# amp1_psu_v0001.net
KiCad netlist of a schematic drawn in EAGLE
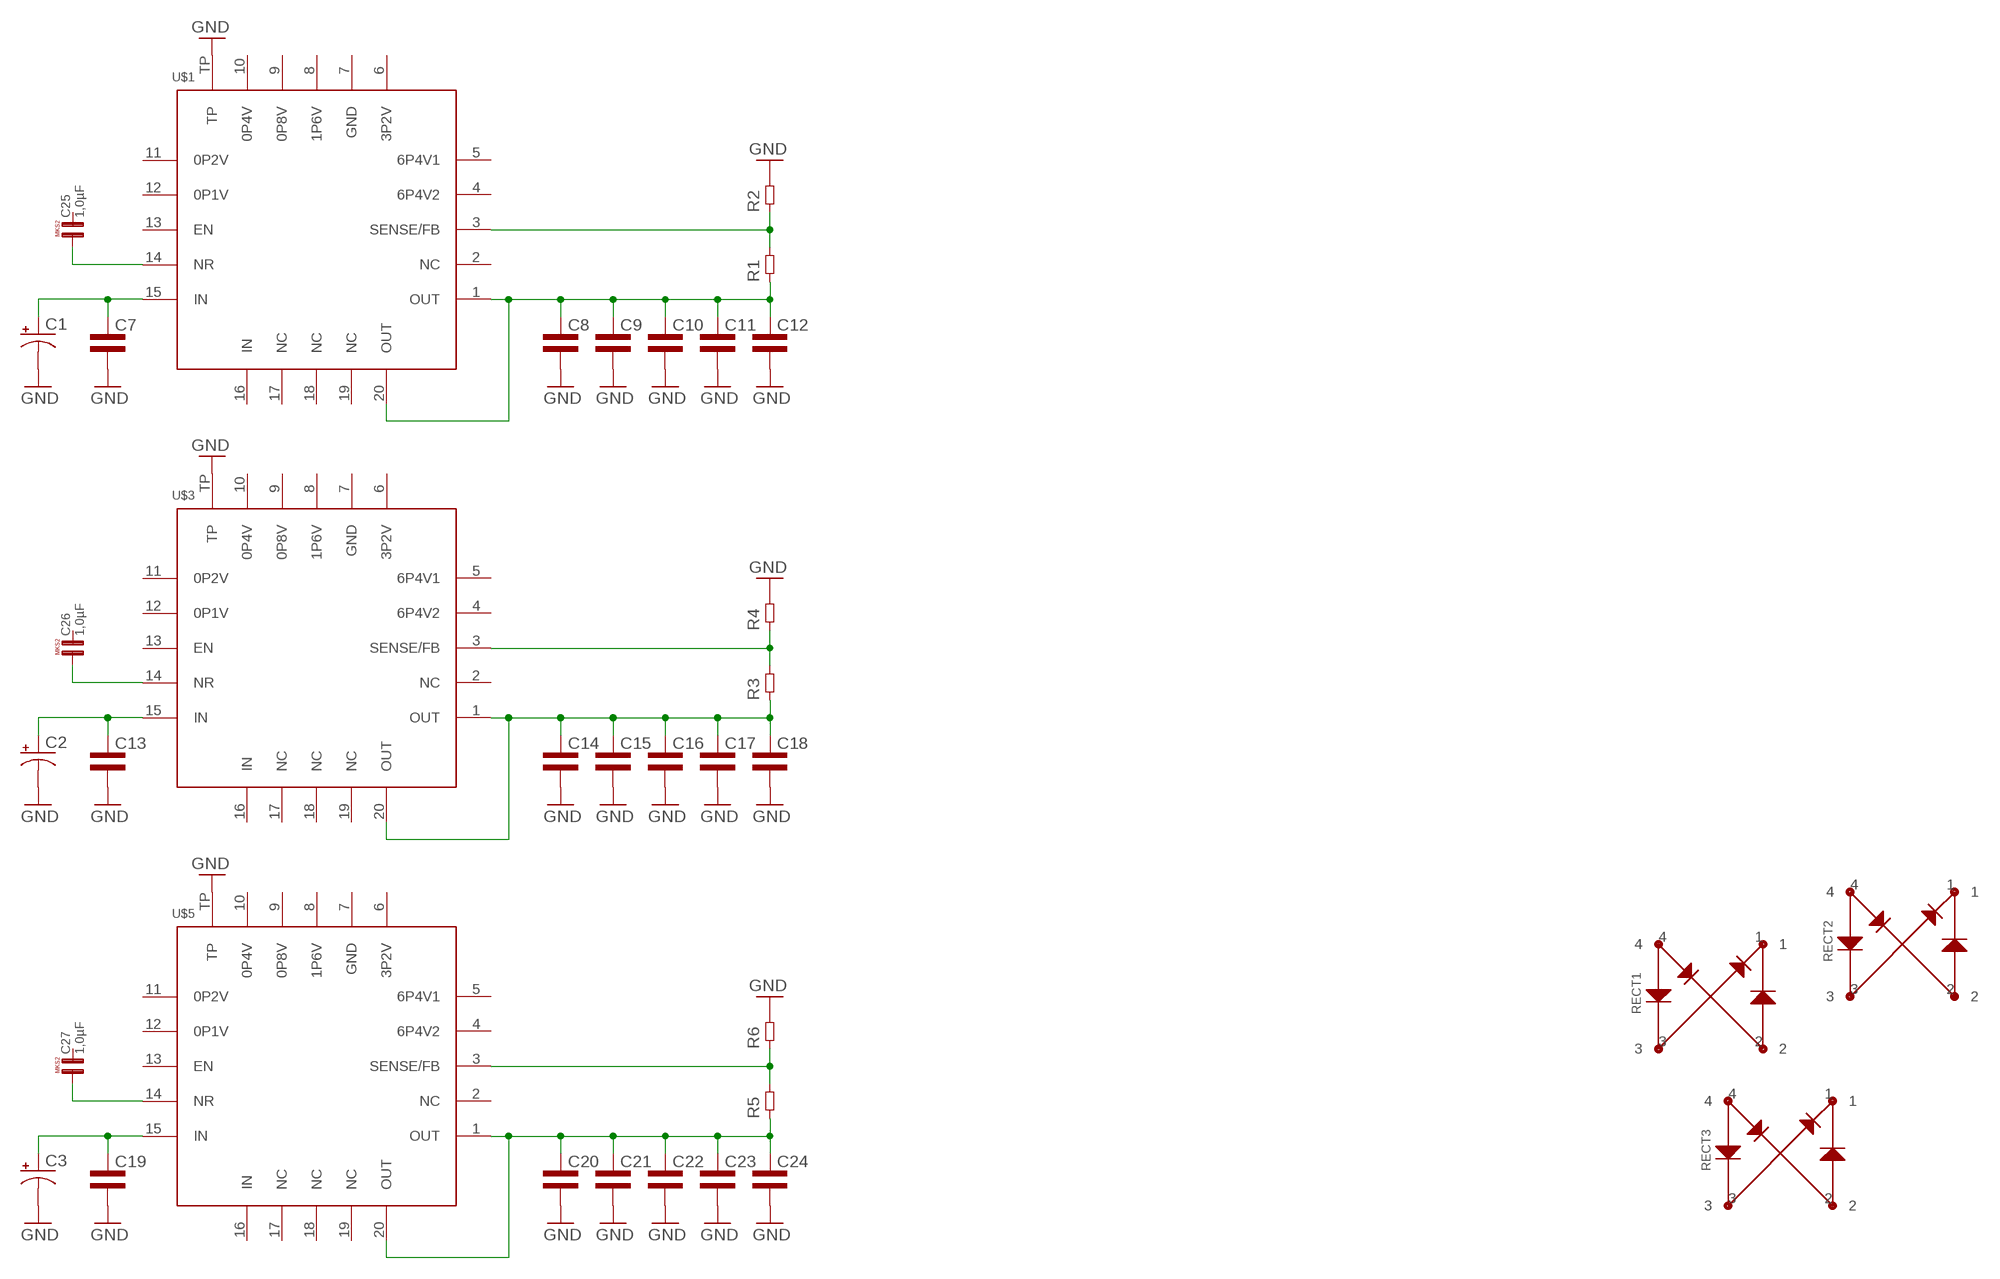
[diagram p0: schematic, sheet 1]
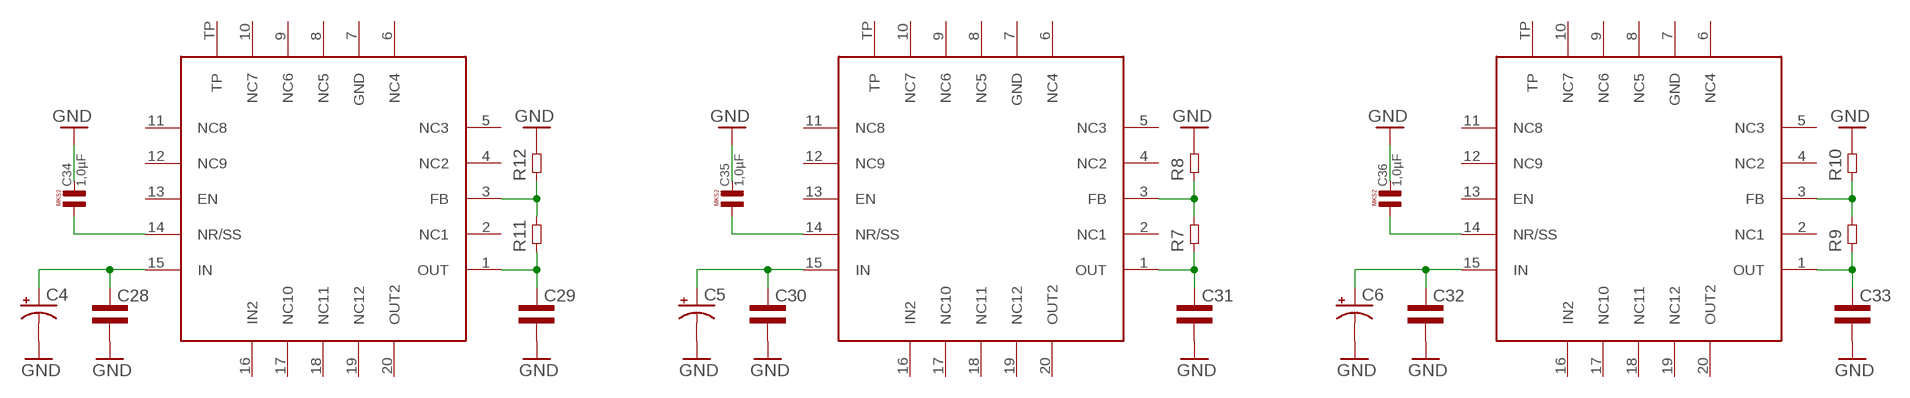
[diagram p1: schematic, sheet 2]

(export (version "E")
  (design (tool "Eeschema 10.0.6"))
  (components
    (comp (ref "C1")
      (value "CPOL-USE7.5-18")
      (footprint "eagle-import:E7,5-18")
      (libsource (lib "eagle-import") (part "CPOL-USE7.5-18"))
    )
    (comp (ref "C2")
      (value "CPOL-USE7.5-18")
      (footprint "eagle-import:E7,5-18")
      (libsource (lib "eagle-import") (part "CPOL-USE7.5-18"))
    )
    (comp (ref "C3")
      (value "CPOL-USE7.5-18")
      (footprint "eagle-import:E7,5-18")
      (libsource (lib "eagle-import") (part "CPOL-USE7.5-18"))
    )
    (comp (ref "C7")
      (value "CAP0805L3")
      (footprint "eagle-import:0805L3")
      (libsource (lib "eagle-import") (part "CAP0805L3"))
    )
    (comp (ref "C8")
      (value "CAP0805L3")
      (footprint "eagle-import:0805L3")
      (libsource (lib "eagle-import") (part "CAP0805L3"))
    )
    (comp (ref "C9")
      (value "CAP0805L3")
      (footprint "eagle-import:0805L3")
      (libsource (lib "eagle-import") (part "CAP0805L3"))
    )
    (comp (ref "C10")
      (value "CAP0805L3")
      (footprint "eagle-import:0805L3")
      (libsource (lib "eagle-import") (part "CAP0805L3"))
    )
    (comp (ref "C11")
      (value "CAP0805L3")
      (footprint "eagle-import:0805L3")
      (libsource (lib "eagle-import") (part "CAP0805L3"))
    )
    (comp (ref "C12")
      (value "CAP0805L3")
      (footprint "eagle-import:0805L3")
      (libsource (lib "eagle-import") (part "CAP0805L3"))
    )
    (comp (ref "C13")
      (value "CAP0805L3")
      (footprint "eagle-import:0805L3")
      (libsource (lib "eagle-import") (part "CAP0805L3"))
    )
    (comp (ref "C14")
      (value "CAP0805L3")
      (footprint "eagle-import:0805L3")
      (libsource (lib "eagle-import") (part "CAP0805L3"))
    )
    (comp (ref "C15")
      (value "CAP0805L3")
      (footprint "eagle-import:0805L3")
      (libsource (lib "eagle-import") (part "CAP0805L3"))
    )
    (comp (ref "C16")
      (value "CAP0805L3")
      (footprint "eagle-import:0805L3")
      (libsource (lib "eagle-import") (part "CAP0805L3"))
    )
    (comp (ref "C17")
      (value "CAP0805L3")
      (footprint "eagle-import:0805L3")
      (libsource (lib "eagle-import") (part "CAP0805L3"))
    )
    (comp (ref "C18")
      (value "CAP0805L3")
      (footprint "eagle-import:0805L3")
      (libsource (lib "eagle-import") (part "CAP0805L3"))
    )
    (comp (ref "C19")
      (value "CAP0805L3")
      (footprint "eagle-import:0805L3")
      (libsource (lib "eagle-import") (part "CAP0805L3"))
    )
    (comp (ref "C20")
      (value "CAP0805L3")
      (footprint "eagle-import:0805L3")
      (libsource (lib "eagle-import") (part "CAP0805L3"))
    )
    (comp (ref "C21")
      (value "CAP0805L3")
      (footprint "eagle-import:0805L3")
      (libsource (lib "eagle-import") (part "CAP0805L3"))
    )
    (comp (ref "C22")
      (value "CAP0805L3")
      (footprint "eagle-import:0805L3")
      (libsource (lib "eagle-import") (part "CAP0805L3"))
    )
    (comp (ref "C23")
      (value "CAP0805L3")
      (footprint "eagle-import:0805L3")
      (libsource (lib "eagle-import") (part "CAP0805L3"))
    )
    (comp (ref "C24")
      (value "CAP0805L3")
      (footprint "eagle-import:0805L3")
      (libsource (lib "eagle-import") (part "CAP0805L3"))
    )
    (comp (ref "C25")
      (value "1,0µF")
      (footprint "eagle-import:R5B5")
      (libsource (lib "eagle-import") (part "1,0µF"))
    )
    (comp (ref "C26")
      (value "1,0µF")
      (footprint "eagle-import:R5B5")
      (libsource (lib "eagle-import") (part "1,0µF"))
    )
    (comp (ref "C27")
      (value "1,0µF")
      (footprint "eagle-import:R5B5")
      (libsource (lib "eagle-import") (part "1,0µF"))
    )
    (comp (ref "R1")
      (value "RES0805L3")
      (footprint "eagle-import:0805L3")
      (libsource (lib "eagle-import") (part "RES0805L3"))
    )
    (comp (ref "R2")
      (value "RES0805L3")
      (footprint "eagle-import:0805L3")
      (libsource (lib "eagle-import") (part "RES0805L3"))
    )
    (comp (ref "R3")
      (value "RES0805L3")
      (footprint "eagle-import:0805L3")
      (libsource (lib "eagle-import") (part "RES0805L3"))
    )
    (comp (ref "R4")
      (value "RES0805L3")
      (footprint "eagle-import:0805L3")
      (libsource (lib "eagle-import") (part "RES0805L3"))
    )
    (comp (ref "R5")
      (value "RES0805L3")
      (footprint "eagle-import:0805L3")
      (libsource (lib "eagle-import") (part "RES0805L3"))
    )
    (comp (ref "R6")
      (value "RES0805L3")
      (footprint "eagle-import:0805L3")
      (libsource (lib "eagle-import") (part "RES0805L3"))
    )
    (comp (ref "RECT1")
      (value "RECTIFIER_Z4GP206")
      (footprint "eagle-import:RECTIFIER_ABS-4")
      (libsource (lib "eagle-import") (part "RECTIFIER_Z4GP206"))
    )
    (comp (ref "RECT2")
      (value "RECTIFIER_Z4GP206")
      (footprint "eagle-import:RECTIFIER_ABS-4")
      (libsource (lib "eagle-import") (part "RECTIFIER_Z4GP206"))
    )
    (comp (ref "RECT3")
      (value "RECTIFIER_Z4GP206")
      (footprint "eagle-import:RECTIFIER_ABS-4")
      (libsource (lib "eagle-import") (part "RECTIFIER_Z4GP206"))
    )
    (comp (ref "U$1")
      (value "POWER-SUPPLY_POS_V1_TI_LDO_TPS7A4700")
      (footprint "eagle-import:POWER-SUPPLY_POS_V1_TI_LDO_VQFN-20")
      (libsource (lib "eagle-import") (part "POWER-SUPPLY_POS_V1_TI_LDO_TPS7A4700"))
    )
    (comp (ref "U$3")
      (value "POWER-SUPPLY_POS_V1_TI_LDO_TPS7A4700")
      (footprint "eagle-import:POWER-SUPPLY_POS_V1_TI_LDO_VQFN-20")
      (libsource (lib "eagle-import") (part "POWER-SUPPLY_POS_V1_TI_LDO_TPS7A4700"))
    )
    (comp (ref "U$5")
      (value "POWER-SUPPLY_POS_V1_TI_LDO_TPS7A4700")
      (footprint "eagle-import:POWER-SUPPLY_POS_V1_TI_LDO_VQFN-20")
      (libsource (lib "eagle-import") (part "POWER-SUPPLY_POS_V1_TI_LDO_TPS7A4700"))
    )
    (comp (ref "C4")
      (value "CPOL-USE7.5-18")
      (footprint "eagle-import:E7,5-18")
      (libsource (lib "eagle-import") (part "CPOL-USE7.5-18"))
    )
    (comp (ref "C5")
      (value "CPOL-USE7.5-18")
      (footprint "eagle-import:E7,5-18")
      (libsource (lib "eagle-import") (part "CPOL-USE7.5-18"))
    )
    (comp (ref "C6")
      (value "CPOL-USE7.5-18")
      (footprint "eagle-import:E7,5-18")
      (libsource (lib "eagle-import") (part "CPOL-USE7.5-18"))
    )
    (comp (ref "C28")
      (value "CAP0805L3")
      (footprint "eagle-import:0805L3")
      (libsource (lib "eagle-import") (part "CAP0805L3"))
    )
    (comp (ref "C29")
      (value "CAP0805L3")
      (footprint "eagle-import:0805L3")
      (libsource (lib "eagle-import") (part "CAP0805L3"))
    )
    (comp (ref "C30")
      (value "CAP0805L3")
      (footprint "eagle-import:0805L3")
      (libsource (lib "eagle-import") (part "CAP0805L3"))
    )
    (comp (ref "C31")
      (value "CAP0805L3")
      (footprint "eagle-import:0805L3")
      (libsource (lib "eagle-import") (part "CAP0805L3"))
    )
    (comp (ref "C32")
      (value "CAP0805L3")
      (footprint "eagle-import:0805L3")
      (libsource (lib "eagle-import") (part "CAP0805L3"))
    )
    (comp (ref "C33")
      (value "CAP0805L3")
      (footprint "eagle-import:0805L3")
      (libsource (lib "eagle-import") (part "CAP0805L3"))
    )
    (comp (ref "C34")
      (value "1,0µF")
      (footprint "eagle-import:R5B5")
      (libsource (lib "eagle-import") (part "1,0µF"))
    )
    (comp (ref "C35")
      (value "1,0µF")
      (footprint "eagle-import:R5B5")
      (libsource (lib "eagle-import") (part "1,0µF"))
    )
    (comp (ref "C36")
      (value "1,0µF")
      (footprint "eagle-import:R5B5")
      (libsource (lib "eagle-import") (part "1,0µF"))
    )
    (comp (ref "R7")
      (value "RES0805L3")
      (footprint "eagle-import:0805L3")
      (libsource (lib "eagle-import") (part "RES0805L3"))
    )
    (comp (ref "R8")
      (value "RES0805L3")
      (footprint "eagle-import:0805L3")
      (libsource (lib "eagle-import") (part "RES0805L3"))
    )
    (comp (ref "R9")
      (value "RES0805L3")
      (footprint "eagle-import:0805L3")
      (libsource (lib "eagle-import") (part "RES0805L3"))
    )
    (comp (ref "R10")
      (value "RES0805L3")
      (footprint "eagle-import:0805L3")
      (libsource (lib "eagle-import") (part "RES0805L3"))
    )
    (comp (ref "R11")
      (value "RES0805L3")
      (footprint "eagle-import:0805L3")
      (libsource (lib "eagle-import") (part "RES0805L3"))
    )
    (comp (ref "R12")
      (value "RES0805L3")
      (footprint "eagle-import:0805L3")
      (libsource (lib "eagle-import") (part "RES0805L3"))
    )
    (comp (ref "U$6")
      (value "POWER-SUPPLY_POS_V1_TI_LDO_TPS7A3301RGWT")
      (footprint "eagle-import:POWER-SUPPLY_POS_V1_TI_LDO_VQFN-20")
      (libsource (lib "eagle-import") (part "POWER-SUPPLY_POS_V1_TI_LDO_TPS7A3301RGWT"))
    )
    (comp (ref "U$7")
      (value "POWER-SUPPLY_POS_V1_TI_LDO_TPS7A3301RGWT")
      (footprint "eagle-import:POWER-SUPPLY_POS_V1_TI_LDO_VQFN-20")
      (libsource (lib "eagle-import") (part "POWER-SUPPLY_POS_V1_TI_LDO_TPS7A3301RGWT"))
    )
    (comp (ref "U$8")
      (value "POWER-SUPPLY_POS_V1_TI_LDO_TPS7A3301RGWT")
      (footprint "eagle-import:POWER-SUPPLY_POS_V1_TI_LDO_VQFN-20")
      (libsource (lib "eagle-import") (part "POWER-SUPPLY_POS_V1_TI_LDO_TPS7A3301RGWT"))
    )
  )
  (nets
    (net (code "1") (name "GND") (class "Default")
      (node (ref "C1") (pin "-") (pinfunction "-_-") (pintype "passive"))
      (node (ref "C10") (pin "2") (pinfunction "2_2") (pintype "bidirectional"))
      (node (ref "C11") (pin "2") (pinfunction "2_2") (pintype "bidirectional"))
      (node (ref "C12") (pin "2") (pinfunction "2_2") (pintype "bidirectional"))
      (node (ref "C13") (pin "2") (pinfunction "2_2") (pintype "bidirectional"))
      (node (ref "C14") (pin "2") (pinfunction "2_2") (pintype "bidirectional"))
      (node (ref "C15") (pin "2") (pinfunction "2_2") (pintype "bidirectional"))
      (node (ref "C16") (pin "2") (pinfunction "2_2") (pintype "bidirectional"))
      (node (ref "C17") (pin "2") (pinfunction "2_2") (pintype "bidirectional"))
      (node (ref "C18") (pin "2") (pinfunction "2_2") (pintype "bidirectional"))
      (node (ref "C19") (pin "2") (pinfunction "2_2") (pintype "bidirectional"))
      (node (ref "C2") (pin "-") (pinfunction "-_-") (pintype "passive"))
      (node (ref "C20") (pin "2") (pinfunction "2_2") (pintype "bidirectional"))
      (node (ref "C21") (pin "2") (pinfunction "2_2") (pintype "bidirectional"))
      (node (ref "C22") (pin "2") (pinfunction "2_2") (pintype "bidirectional"))
      (node (ref "C23") (pin "2") (pinfunction "2_2") (pintype "bidirectional"))
      (node (ref "C24") (pin "2") (pinfunction "2_2") (pintype "bidirectional"))
      (node (ref "C28") (pin "2") (pinfunction "2_2") (pintype "bidirectional"))
      (node (ref "C29") (pin "2") (pinfunction "2_2") (pintype "bidirectional"))
      (node (ref "C3") (pin "-") (pinfunction "-_-") (pintype "passive"))
      (node (ref "C30") (pin "2") (pinfunction "2_2") (pintype "bidirectional"))
      (node (ref "C31") (pin "2") (pinfunction "2_2") (pintype "bidirectional"))
      (node (ref "C32") (pin "2") (pinfunction "2_2") (pintype "bidirectional"))
      (node (ref "C33") (pin "2") (pinfunction "2_2") (pintype "bidirectional"))
      (node (ref "C34") (pin "2") (pinfunction "2_2") (pintype "passive"))
      (node (ref "C35") (pin "2") (pinfunction "2_2") (pintype "passive"))
      (node (ref "C36") (pin "2") (pinfunction "2_2") (pintype "passive"))
      (node (ref "C4") (pin "-") (pinfunction "-_-") (pintype "passive"))
      (node (ref "C5") (pin "-") (pinfunction "-_-") (pintype "passive"))
      (node (ref "C6") (pin "-") (pinfunction "-_-") (pintype "passive"))
      (node (ref "C7") (pin "2") (pinfunction "2_2") (pintype "bidirectional"))
      (node (ref "C8") (pin "2") (pinfunction "2_2") (pintype "bidirectional"))
      (node (ref "C9") (pin "2") (pinfunction "2_2") (pintype "bidirectional"))
      (node (ref "R10") (pin "2") (pinfunction "2_2") (pintype "bidirectional"))
      (node (ref "R12") (pin "2") (pinfunction "2_2") (pintype "bidirectional"))
      (node (ref "R2") (pin "2") (pinfunction "2_2") (pintype "bidirectional"))
      (node (ref "R4") (pin "2") (pinfunction "2_2") (pintype "bidirectional"))
      (node (ref "R6") (pin "2") (pinfunction "2_2") (pintype "bidirectional"))
      (node (ref "R8") (pin "2") (pinfunction "2_2") (pintype "bidirectional"))
      (node (ref "U$1") (pin "TP") (pinfunction "TP_TP") (pintype "bidirectional"))
      (node (ref "U$3") (pin "TP") (pinfunction "TP_TP") (pintype "bidirectional"))
      (node (ref "U$5") (pin "TP") (pinfunction "TP_TP") (pintype "bidirectional"))
    )
    (net (code "2") (name "Net-(C1-Pad+)") (class "Default")
      (node (ref "C1") (pin "+") (pinfunction "+_+") (pintype "passive"))
      (node (ref "C7") (pin "1") (pinfunction "1_1") (pintype "bidirectional"))
      (node (ref "U$1") (pin "15") (pinfunction "IN_15") (pintype "bidirectional"))
    )
    (net (code "3") (name "Net-(C10-Pad1)") (class "Default")
      (node (ref "C10") (pin "1") (pinfunction "1_1") (pintype "bidirectional"))
      (node (ref "C11") (pin "1") (pinfunction "1_1") (pintype "bidirectional"))
      (node (ref "C12") (pin "1") (pinfunction "1_1") (pintype "bidirectional"))
      (node (ref "C8") (pin "1") (pinfunction "1_1") (pintype "bidirectional"))
      (node (ref "C9") (pin "1") (pinfunction "1_1") (pintype "bidirectional"))
      (node (ref "R1") (pin "1") (pinfunction "1_1") (pintype "bidirectional"))
      (node (ref "U$1") (pin "1") (pinfunction "OUT_1") (pintype "bidirectional"))
      (node (ref "U$1") (pin "20") (pinfunction "OUT_20") (pintype "bidirectional"))
    )
    (net (code "4") (name "Net-(C13-Pad1)") (class "Default")
      (node (ref "C13") (pin "1") (pinfunction "1_1") (pintype "bidirectional"))
      (node (ref "C2") (pin "+") (pinfunction "+_+") (pintype "passive"))
      (node (ref "U$3") (pin "15") (pinfunction "IN_15") (pintype "bidirectional"))
    )
    (net (code "5") (name "Net-(C14-Pad1)") (class "Default")
      (node (ref "C14") (pin "1") (pinfunction "1_1") (pintype "bidirectional"))
      (node (ref "C15") (pin "1") (pinfunction "1_1") (pintype "bidirectional"))
      (node (ref "C16") (pin "1") (pinfunction "1_1") (pintype "bidirectional"))
      (node (ref "C17") (pin "1") (pinfunction "1_1") (pintype "bidirectional"))
      (node (ref "C18") (pin "1") (pinfunction "1_1") (pintype "bidirectional"))
      (node (ref "R3") (pin "1") (pinfunction "1_1") (pintype "bidirectional"))
      (node (ref "U$3") (pin "1") (pinfunction "OUT_1") (pintype "bidirectional"))
      (node (ref "U$3") (pin "20") (pinfunction "OUT_20") (pintype "bidirectional"))
    )
    (net (code "6") (name "Net-(C19-Pad1)") (class "Default")
      (node (ref "C19") (pin "1") (pinfunction "1_1") (pintype "bidirectional"))
      (node (ref "C3") (pin "+") (pinfunction "+_+") (pintype "passive"))
      (node (ref "U$5") (pin "15") (pinfunction "IN_15") (pintype "bidirectional"))
    )
    (net (code "7") (name "Net-(C20-Pad1)") (class "Default")
      (node (ref "C20") (pin "1") (pinfunction "1_1") (pintype "bidirectional"))
      (node (ref "C21") (pin "1") (pinfunction "1_1") (pintype "bidirectional"))
      (node (ref "C22") (pin "1") (pinfunction "1_1") (pintype "bidirectional"))
      (node (ref "C23") (pin "1") (pinfunction "1_1") (pintype "bidirectional"))
      (node (ref "C24") (pin "1") (pinfunction "1_1") (pintype "bidirectional"))
      (node (ref "R5") (pin "1") (pinfunction "1_1") (pintype "bidirectional"))
      (node (ref "U$5") (pin "1") (pinfunction "OUT_1") (pintype "bidirectional"))
      (node (ref "U$5") (pin "20") (pinfunction "OUT_20") (pintype "bidirectional"))
    )
    (net (code "8") (name "Net-(U$1-NR)") (class "Default")
      (node (ref "C25") (pin "1") (pinfunction "1_1") (pintype "passive"))
      (node (ref "U$1") (pin "14") (pinfunction "NR_14") (pintype "bidirectional"))
    )
    (net (code "9") (name "Net-(U$1-SENSE{slash}FB)") (class "Default")
      (node (ref "R1") (pin "2") (pinfunction "2_2") (pintype "bidirectional"))
      (node (ref "R2") (pin "1") (pinfunction "1_1") (pintype "bidirectional"))
      (node (ref "U$1") (pin "3") (pinfunction "SENSE/FB_3") (pintype "bidirectional"))
    )
    (net (code "10") (name "Net-(U$3-NR)") (class "Default")
      (node (ref "C26") (pin "1") (pinfunction "1_1") (pintype "passive"))
      (node (ref "U$3") (pin "14") (pinfunction "NR_14") (pintype "bidirectional"))
    )
    (net (code "11") (name "Net-(U$3-SENSE{slash}FB)") (class "Default")
      (node (ref "R3") (pin "2") (pinfunction "2_2") (pintype "bidirectional"))
      (node (ref "R4") (pin "1") (pinfunction "1_1") (pintype "bidirectional"))
      (node (ref "U$3") (pin "3") (pinfunction "SENSE/FB_3") (pintype "bidirectional"))
    )
    (net (code "12") (name "Net-(U$5-NR)") (class "Default")
      (node (ref "C27") (pin "1") (pinfunction "1_1") (pintype "passive"))
      (node (ref "U$5") (pin "14") (pinfunction "NR_14") (pintype "bidirectional"))
    )
    (net (code "13") (name "Net-(U$5-SENSE{slash}FB)") (class "Default")
      (node (ref "R5") (pin "2") (pinfunction "2_2") (pintype "bidirectional"))
      (node (ref "R6") (pin "1") (pinfunction "1_1") (pintype "bidirectional"))
      (node (ref "U$5") (pin "3") (pinfunction "SENSE/FB_3") (pintype "bidirectional"))
    )
    (net (code "14") (name "Net-(U$6-FB)") (class "Default")
      (node (ref "R11") (pin "2") (pinfunction "2_2") (pintype "bidirectional"))
      (node (ref "R12") (pin "1") (pinfunction "1_1") (pintype "bidirectional"))
      (node (ref "U$6") (pin "3") (pinfunction "FB_3") (pintype "bidirectional"))
    )
    (net (code "15") (name "Net-(U$6-IN)") (class "Default")
      (node (ref "C28") (pin "1") (pinfunction "1_1") (pintype "bidirectional"))
      (node (ref "C4") (pin "+") (pinfunction "+_+") (pintype "passive"))
      (node (ref "U$6") (pin "15") (pinfunction "IN_15") (pintype "bidirectional"))
    )
    (net (code "16") (name "Net-(U$6-NR{slash}SS)") (class "Default")
      (node (ref "C34") (pin "1") (pinfunction "1_1") (pintype "passive"))
      (node (ref "U$6") (pin "14") (pinfunction "NR/SS_14") (pintype "bidirectional"))
    )
    (net (code "17") (name "Net-(U$6-OUT)") (class "Default")
      (node (ref "C29") (pin "1") (pinfunction "1_1") (pintype "bidirectional"))
      (node (ref "R11") (pin "1") (pinfunction "1_1") (pintype "bidirectional"))
      (node (ref "U$6") (pin "1") (pinfunction "OUT_1") (pintype "bidirectional"))
    )
    (net (code "18") (name "Net-(U$7-FB)") (class "Default")
      (node (ref "R7") (pin "2") (pinfunction "2_2") (pintype "bidirectional"))
      (node (ref "R8") (pin "1") (pinfunction "1_1") (pintype "bidirectional"))
      (node (ref "U$7") (pin "3") (pinfunction "FB_3") (pintype "bidirectional"))
    )
    (net (code "19") (name "Net-(U$7-IN)") (class "Default")
      (node (ref "C30") (pin "1") (pinfunction "1_1") (pintype "bidirectional"))
      (node (ref "C5") (pin "+") (pinfunction "+_+") (pintype "passive"))
      (node (ref "U$7") (pin "15") (pinfunction "IN_15") (pintype "bidirectional"))
    )
    (net (code "20") (name "Net-(U$7-NR{slash}SS)") (class "Default")
      (node (ref "C35") (pin "1") (pinfunction "1_1") (pintype "passive"))
      (node (ref "U$7") (pin "14") (pinfunction "NR/SS_14") (pintype "bidirectional"))
    )
    (net (code "21") (name "Net-(U$7-OUT)") (class "Default")
      (node (ref "C31") (pin "1") (pinfunction "1_1") (pintype "bidirectional"))
      (node (ref "R7") (pin "1") (pinfunction "1_1") (pintype "bidirectional"))
      (node (ref "U$7") (pin "1") (pinfunction "OUT_1") (pintype "bidirectional"))
    )
    (net (code "22") (name "Net-(U$8-FB)") (class "Default")
      (node (ref "R10") (pin "1") (pinfunction "1_1") (pintype "bidirectional"))
      (node (ref "R9") (pin "2") (pinfunction "2_2") (pintype "bidirectional"))
      (node (ref "U$8") (pin "3") (pinfunction "FB_3") (pintype "bidirectional"))
    )
    (net (code "23") (name "Net-(U$8-IN)") (class "Default")
      (node (ref "C32") (pin "1") (pinfunction "1_1") (pintype "bidirectional"))
      (node (ref "C6") (pin "+") (pinfunction "+_+") (pintype "passive"))
      (node (ref "U$8") (pin "15") (pinfunction "IN_15") (pintype "bidirectional"))
    )
    (net (code "24") (name "Net-(U$8-NR{slash}SS)") (class "Default")
      (node (ref "C36") (pin "1") (pinfunction "1_1") (pintype "passive"))
      (node (ref "U$8") (pin "14") (pinfunction "NR/SS_14") (pintype "bidirectional"))
    )
    (net (code "25") (name "Net-(U$8-OUT)") (class "Default")
      (node (ref "C33") (pin "1") (pinfunction "1_1") (pintype "bidirectional"))
      (node (ref "R9") (pin "1") (pinfunction "1_1") (pintype "bidirectional"))
      (node (ref "U$8") (pin "1") (pinfunction "OUT_1") (pintype "bidirectional"))
    )
    (net (code "26") (name "unconnected-(C25-Pad2)") (class "Default")
      (node (ref "C25") (pin "2") (pinfunction "2_2") (pintype "passive"))
    )
    (net (code "27") (name "unconnected-(C26-Pad2)") (class "Default")
      (node (ref "C26") (pin "2") (pinfunction "2_2") (pintype "passive"))
    )
    (net (code "28") (name "unconnected-(C27-Pad2)") (class "Default")
      (node (ref "C27") (pin "2") (pinfunction "2_2") (pintype "passive"))
    )
    (net (code "29") (name "unconnected-(RECT1-Pad1)") (class "Default")
      (node (ref "RECT1") (pin "1") (pinfunction "1_1") (pintype "bidirectional"))
    )
    (net (code "30") (name "unconnected-(RECT1-Pad2)") (class "Default")
      (node (ref "RECT1") (pin "2") (pinfunction "2_2") (pintype "bidirectional"))
    )
    (net (code "31") (name "unconnected-(RECT1-Pad3)") (class "Default")
      (node (ref "RECT1") (pin "3") (pinfunction "3_3") (pintype "bidirectional"))
    )
    (net (code "32") (name "unconnected-(RECT1-Pad4)") (class "Default")
      (node (ref "RECT1") (pin "4") (pinfunction "4_4") (pintype "bidirectional"))
    )
    (net (code "33") (name "unconnected-(RECT2-Pad1)") (class "Default")
      (node (ref "RECT2") (pin "1") (pinfunction "1_1") (pintype "bidirectional"))
    )
    (net (code "34") (name "unconnected-(RECT2-Pad2)") (class "Default")
      (node (ref "RECT2") (pin "2") (pinfunction "2_2") (pintype "bidirectional"))
    )
    (net (code "35") (name "unconnected-(RECT2-Pad3)") (class "Default")
      (node (ref "RECT2") (pin "3") (pinfunction "3_3") (pintype "bidirectional"))
    )
    (net (code "36") (name "unconnected-(RECT2-Pad4)") (class "Default")
      (node (ref "RECT2") (pin "4") (pinfunction "4_4") (pintype "bidirectional"))
    )
    (net (code "37") (name "unconnected-(RECT3-Pad1)") (class "Default")
      (node (ref "RECT3") (pin "1") (pinfunction "1_1") (pintype "bidirectional"))
    )
    (net (code "38") (name "unconnected-(RECT3-Pad2)") (class "Default")
      (node (ref "RECT3") (pin "2") (pinfunction "2_2") (pintype "bidirectional"))
    )
    (net (code "39") (name "unconnected-(RECT3-Pad3)") (class "Default")
      (node (ref "RECT3") (pin "3") (pinfunction "3_3") (pintype "bidirectional"))
    )
    (net (code "40") (name "unconnected-(RECT3-Pad4)") (class "Default")
      (node (ref "RECT3") (pin "4") (pinfunction "4_4") (pintype "bidirectional"))
    )
    (net (code "41") (name "unconnected-(U$1-0P1V-Pad12)") (class "Default")
      (node (ref "U$1") (pin "12") (pinfunction "0P1V_12") (pintype "bidirectional"))
    )
    (net (code "42") (name "unconnected-(U$1-0P2V-Pad11)") (class "Default")
      (node (ref "U$1") (pin "11") (pinfunction "0P2V_11") (pintype "bidirectional"))
    )
    (net (code "43") (name "unconnected-(U$1-0P4V-Pad10)") (class "Default")
      (node (ref "U$1") (pin "10") (pinfunction "0P4V_10") (pintype "bidirectional"))
    )
    (net (code "44") (name "unconnected-(U$1-0P8V-Pad9)") (class "Default")
      (node (ref "U$1") (pin "9") (pinfunction "0P8V_9") (pintype "bidirectional"))
    )
    (net (code "45") (name "unconnected-(U$1-1P6V-Pad8)") (class "Default")
      (node (ref "U$1") (pin "8") (pinfunction "1P6V_8") (pintype "bidirectional"))
    )
    (net (code "46") (name "unconnected-(U$1-3P2V-Pad6)") (class "Default")
      (node (ref "U$1") (pin "6") (pinfunction "3P2V_6") (pintype "bidirectional"))
    )
    (net (code "47") (name "unconnected-(U$1-6P4V1-Pad5)") (class "Default")
      (node (ref "U$1") (pin "5") (pinfunction "6P4V1_5") (pintype "bidirectional"))
    )
    (net (code "48") (name "unconnected-(U$1-6P4V2-Pad4)") (class "Default")
      (node (ref "U$1") (pin "4") (pinfunction "6P4V2_4") (pintype "bidirectional"))
    )
    (net (code "49") (name "unconnected-(U$1-EN-Pad13)") (class "Default")
      (node (ref "U$1") (pin "13") (pinfunction "EN_13") (pintype "bidirectional"))
    )
    (net (code "50") (name "unconnected-(U$1-GND-Pad7)") (class "Default")
      (node (ref "U$1") (pin "7") (pinfunction "GND_7") (pintype "bidirectional"))
    )
    (net (code "51") (name "unconnected-(U$1-IN-Pad16)") (class "Default")
      (node (ref "U$1") (pin "16") (pinfunction "IN_16") (pintype "bidirectional"))
    )
    (net (code "52") (name "unconnected-(U$1-NC-Pad2)") (class "Default")
      (node (ref "U$1") (pin "2") (pinfunction "NC_2") (pintype "bidirectional"))
    )
    (net (code "53") (name "unconnected-(U$1-NC-Pad17)") (class "Default")
      (node (ref "U$1") (pin "17") (pinfunction "NC_17") (pintype "bidirectional"))
    )
    (net (code "54") (name "unconnected-(U$1-NC-Pad18)") (class "Default")
      (node (ref "U$1") (pin "18") (pinfunction "NC_18") (pintype "bidirectional"))
    )
    (net (code "55") (name "unconnected-(U$1-NC-Pad19)") (class "Default")
      (node (ref "U$1") (pin "19") (pinfunction "NC_19") (pintype "bidirectional"))
    )
    (net (code "56") (name "unconnected-(U$3-0P1V-Pad12)") (class "Default")
      (node (ref "U$3") (pin "12") (pinfunction "0P1V_12") (pintype "bidirectional"))
    )
    (net (code "57") (name "unconnected-(U$3-0P2V-Pad11)") (class "Default")
      (node (ref "U$3") (pin "11") (pinfunction "0P2V_11") (pintype "bidirectional"))
    )
    (net (code "58") (name "unconnected-(U$3-0P4V-Pad10)") (class "Default")
      (node (ref "U$3") (pin "10") (pinfunction "0P4V_10") (pintype "bidirectional"))
    )
    (net (code "59") (name "unconnected-(U$3-0P8V-Pad9)") (class "Default")
      (node (ref "U$3") (pin "9") (pinfunction "0P8V_9") (pintype "bidirectional"))
    )
    (net (code "60") (name "unconnected-(U$3-1P6V-Pad8)") (class "Default")
      (node (ref "U$3") (pin "8") (pinfunction "1P6V_8") (pintype "bidirectional"))
    )
    (net (code "61") (name "unconnected-(U$3-3P2V-Pad6)") (class "Default")
      (node (ref "U$3") (pin "6") (pinfunction "3P2V_6") (pintype "bidirectional"))
    )
    (net (code "62") (name "unconnected-(U$3-6P4V1-Pad5)") (class "Default")
      (node (ref "U$3") (pin "5") (pinfunction "6P4V1_5") (pintype "bidirectional"))
    )
    (net (code "63") (name "unconnected-(U$3-6P4V2-Pad4)") (class "Default")
      (node (ref "U$3") (pin "4") (pinfunction "6P4V2_4") (pintype "bidirectional"))
    )
    (net (code "64") (name "unconnected-(U$3-EN-Pad13)") (class "Default")
      (node (ref "U$3") (pin "13") (pinfunction "EN_13") (pintype "bidirectional"))
    )
    (net (code "65") (name "unconnected-(U$3-GND-Pad7)") (class "Default")
      (node (ref "U$3") (pin "7") (pinfunction "GND_7") (pintype "bidirectional"))
    )
    (net (code "66") (name "unconnected-(U$3-IN-Pad16)") (class "Default")
      (node (ref "U$3") (pin "16") (pinfunction "IN_16") (pintype "bidirectional"))
    )
    (net (code "67") (name "unconnected-(U$3-NC-Pad2)") (class "Default")
      (node (ref "U$3") (pin "2") (pinfunction "NC_2") (pintype "bidirectional"))
    )
    (net (code "68") (name "unconnected-(U$3-NC-Pad17)") (class "Default")
      (node (ref "U$3") (pin "17") (pinfunction "NC_17") (pintype "bidirectional"))
    )
    (net (code "69") (name "unconnected-(U$3-NC-Pad18)") (class "Default")
      (node (ref "U$3") (pin "18") (pinfunction "NC_18") (pintype "bidirectional"))
    )
    (net (code "70") (name "unconnected-(U$3-NC-Pad19)") (class "Default")
      (node (ref "U$3") (pin "19") (pinfunction "NC_19") (pintype "bidirectional"))
    )
    (net (code "71") (name "unconnected-(U$5-0P1V-Pad12)") (class "Default")
      (node (ref "U$5") (pin "12") (pinfunction "0P1V_12") (pintype "bidirectional"))
    )
    (net (code "72") (name "unconnected-(U$5-0P2V-Pad11)") (class "Default")
      (node (ref "U$5") (pin "11") (pinfunction "0P2V_11") (pintype "bidirectional"))
    )
    (net (code "73") (name "unconnected-(U$5-0P4V-Pad10)") (class "Default")
      (node (ref "U$5") (pin "10") (pinfunction "0P4V_10") (pintype "bidirectional"))
    )
    (net (code "74") (name "unconnected-(U$5-0P8V-Pad9)") (class "Default")
      (node (ref "U$5") (pin "9") (pinfunction "0P8V_9") (pintype "bidirectional"))
    )
    (net (code "75") (name "unconnected-(U$5-1P6V-Pad8)") (class "Default")
      (node (ref "U$5") (pin "8") (pinfunction "1P6V_8") (pintype "bidirectional"))
    )
    (net (code "76") (name "unconnected-(U$5-3P2V-Pad6)") (class "Default")
      (node (ref "U$5") (pin "6") (pinfunction "3P2V_6") (pintype "bidirectional"))
    )
    (net (code "77") (name "unconnected-(U$5-6P4V1-Pad5)") (class "Default")
      (node (ref "U$5") (pin "5") (pinfunction "6P4V1_5") (pintype "bidirectional"))
    )
    (net (code "78") (name "unconnected-(U$5-6P4V2-Pad4)") (class "Default")
      (node (ref "U$5") (pin "4") (pinfunction "6P4V2_4") (pintype "bidirectional"))
    )
    (net (code "79") (name "unconnected-(U$5-EN-Pad13)") (class "Default")
      (node (ref "U$5") (pin "13") (pinfunction "EN_13") (pintype "bidirectional"))
    )
    (net (code "80") (name "unconnected-(U$5-GND-Pad7)") (class "Default")
      (node (ref "U$5") (pin "7") (pinfunction "GND_7") (pintype "bidirectional"))
    )
    (net (code "81") (name "unconnected-(U$5-IN-Pad16)") (class "Default")
      (node (ref "U$5") (pin "16") (pinfunction "IN_16") (pintype "bidirectional"))
    )
    (net (code "82") (name "unconnected-(U$5-NC-Pad2)") (class "Default")
      (node (ref "U$5") (pin "2") (pinfunction "NC_2") (pintype "bidirectional"))
    )
    (net (code "83") (name "unconnected-(U$5-NC-Pad17)") (class "Default")
      (node (ref "U$5") (pin "17") (pinfunction "NC_17") (pintype "bidirectional"))
    )
    (net (code "84") (name "unconnected-(U$5-NC-Pad18)") (class "Default")
      (node (ref "U$5") (pin "18") (pinfunction "NC_18") (pintype "bidirectional"))
    )
    (net (code "85") (name "unconnected-(U$5-NC-Pad19)") (class "Default")
      (node (ref "U$5") (pin "19") (pinfunction "NC_19") (pintype "bidirectional"))
    )
    (net (code "86") (name "unconnected-(U$6-EN-Pad13)") (class "Default")
      (node (ref "U$6") (pin "13") (pinfunction "EN_13") (pintype "bidirectional"))
    )
    (net (code "87") (name "unconnected-(U$6-GND-Pad7)") (class "Default")
      (node (ref "U$6") (pin "7") (pinfunction "GND_7") (pintype "bidirectional"))
    )
    (net (code "88") (name "unconnected-(U$6-IN2-Pad16)") (class "Default")
      (node (ref "U$6") (pin "16") (pinfunction "IN2_16") (pintype "bidirectional"))
    )
    (net (code "89") (name "unconnected-(U$6-NC1-Pad2)") (class "Default")
      (node (ref "U$6") (pin "2") (pinfunction "NC1_2") (pintype "bidirectional"))
    )
    (net (code "90") (name "unconnected-(U$6-NC2-Pad4)") (class "Default")
      (node (ref "U$6") (pin "4") (pinfunction "NC2_4") (pintype "bidirectional"))
    )
    (net (code "91") (name "unconnected-(U$6-NC3-Pad5)") (class "Default")
      (node (ref "U$6") (pin "5") (pinfunction "NC3_5") (pintype "bidirectional"))
    )
    (net (code "92") (name "unconnected-(U$6-NC4-Pad6)") (class "Default")
      (node (ref "U$6") (pin "6") (pinfunction "NC4_6") (pintype "bidirectional"))
    )
    (net (code "93") (name "unconnected-(U$6-NC5-Pad8)") (class "Default")
      (node (ref "U$6") (pin "8") (pinfunction "NC5_8") (pintype "bidirectional"))
    )
    (net (code "94") (name "unconnected-(U$6-NC6-Pad9)") (class "Default")
      (node (ref "U$6") (pin "9") (pinfunction "NC6_9") (pintype "bidirectional"))
    )
    (net (code "95") (name "unconnected-(U$6-NC7-Pad10)") (class "Default")
      (node (ref "U$6") (pin "10") (pinfunction "NC7_10") (pintype "bidirectional"))
    )
    (net (code "96") (name "unconnected-(U$6-NC8-Pad11)") (class "Default")
      (node (ref "U$6") (pin "11") (pinfunction "NC8_11") (pintype "bidirectional"))
    )
    (net (code "97") (name "unconnected-(U$6-NC9-Pad12)") (class "Default")
      (node (ref "U$6") (pin "12") (pinfunction "NC9_12") (pintype "bidirectional"))
    )
    (net (code "98") (name "unconnected-(U$6-NC10-Pad17)") (class "Default")
      (node (ref "U$6") (pin "17") (pinfunction "NC10_17") (pintype "bidirectional"))
    )
    (net (code "99") (name "unconnected-(U$6-NC11-Pad18)") (class "Default")
      (node (ref "U$6") (pin "18") (pinfunction "NC11_18") (pintype "bidirectional"))
    )
    (net (code "100") (name "unconnected-(U$6-NC12-Pad19)") (class "Default")
      (node (ref "U$6") (pin "19") (pinfunction "NC12_19") (pintype "bidirectional"))
    )
    (net (code "101") (name "unconnected-(U$6-OUT2-Pad20)") (class "Default")
      (node (ref "U$6") (pin "20") (pinfunction "OUT2_20") (pintype "bidirectional"))
    )
    (net (code "102") (name "unconnected-(U$6-PadTP)") (class "Default")
      (node (ref "U$6") (pin "TP") (pinfunction "TP_TP") (pintype "bidirectional"))
    )
    (net (code "103") (name "unconnected-(U$7-EN-Pad13)") (class "Default")
      (node (ref "U$7") (pin "13") (pinfunction "EN_13") (pintype "bidirectional"))
    )
    (net (code "104") (name "unconnected-(U$7-GND-Pad7)") (class "Default")
      (node (ref "U$7") (pin "7") (pinfunction "GND_7") (pintype "bidirectional"))
    )
    (net (code "105") (name "unconnected-(U$7-IN2-Pad16)") (class "Default")
      (node (ref "U$7") (pin "16") (pinfunction "IN2_16") (pintype "bidirectional"))
    )
    (net (code "106") (name "unconnected-(U$7-NC1-Pad2)") (class "Default")
      (node (ref "U$7") (pin "2") (pinfunction "NC1_2") (pintype "bidirectional"))
    )
    (net (code "107") (name "unconnected-(U$7-NC2-Pad4)") (class "Default")
      (node (ref "U$7") (pin "4") (pinfunction "NC2_4") (pintype "bidirectional"))
    )
    (net (code "108") (name "unconnected-(U$7-NC3-Pad5)") (class "Default")
      (node (ref "U$7") (pin "5") (pinfunction "NC3_5") (pintype "bidirectional"))
    )
    (net (code "109") (name "unconnected-(U$7-NC4-Pad6)") (class "Default")
      (node (ref "U$7") (pin "6") (pinfunction "NC4_6") (pintype "bidirectional"))
    )
    (net (code "110") (name "unconnected-(U$7-NC5-Pad8)") (class "Default")
      (node (ref "U$7") (pin "8") (pinfunction "NC5_8") (pintype "bidirectional"))
    )
    (net (code "111") (name "unconnected-(U$7-NC6-Pad9)") (class "Default")
      (node (ref "U$7") (pin "9") (pinfunction "NC6_9") (pintype "bidirectional"))
    )
    (net (code "112") (name "unconnected-(U$7-NC7-Pad10)") (class "Default")
      (node (ref "U$7") (pin "10") (pinfunction "NC7_10") (pintype "bidirectional"))
    )
    (net (code "113") (name "unconnected-(U$7-NC8-Pad11)") (class "Default")
      (node (ref "U$7") (pin "11") (pinfunction "NC8_11") (pintype "bidirectional"))
    )
    (net (code "114") (name "unconnected-(U$7-NC9-Pad12)") (class "Default")
      (node (ref "U$7") (pin "12") (pinfunction "NC9_12") (pintype "bidirectional"))
    )
    (net (code "115") (name "unconnected-(U$7-NC10-Pad17)") (class "Default")
      (node (ref "U$7") (pin "17") (pinfunction "NC10_17") (pintype "bidirectional"))
    )
    (net (code "116") (name "unconnected-(U$7-NC11-Pad18)") (class "Default")
      (node (ref "U$7") (pin "18") (pinfunction "NC11_18") (pintype "bidirectional"))
    )
    (net (code "117") (name "unconnected-(U$7-NC12-Pad19)") (class "Default")
      (node (ref "U$7") (pin "19") (pinfunction "NC12_19") (pintype "bidirectional"))
    )
    (net (code "118") (name "unconnected-(U$7-OUT2-Pad20)") (class "Default")
      (node (ref "U$7") (pin "20") (pinfunction "OUT2_20") (pintype "bidirectional"))
    )
    (net (code "119") (name "unconnected-(U$7-PadTP)") (class "Default")
      (node (ref "U$7") (pin "TP") (pinfunction "TP_TP") (pintype "bidirectional"))
    )
    (net (code "120") (name "unconnected-(U$8-EN-Pad13)") (class "Default")
      (node (ref "U$8") (pin "13") (pinfunction "EN_13") (pintype "bidirectional"))
    )
    (net (code "121") (name "unconnected-(U$8-GND-Pad7)") (class "Default")
      (node (ref "U$8") (pin "7") (pinfunction "GND_7") (pintype "bidirectional"))
    )
    (net (code "122") (name "unconnected-(U$8-IN2-Pad16)") (class "Default")
      (node (ref "U$8") (pin "16") (pinfunction "IN2_16") (pintype "bidirectional"))
    )
    (net (code "123") (name "unconnected-(U$8-NC1-Pad2)") (class "Default")
      (node (ref "U$8") (pin "2") (pinfunction "NC1_2") (pintype "bidirectional"))
    )
    (net (code "124") (name "unconnected-(U$8-NC2-Pad4)") (class "Default")
      (node (ref "U$8") (pin "4") (pinfunction "NC2_4") (pintype "bidirectional"))
    )
    (net (code "125") (name "unconnected-(U$8-NC3-Pad5)") (class "Default")
      (node (ref "U$8") (pin "5") (pinfunction "NC3_5") (pintype "bidirectional"))
    )
    (net (code "126") (name "unconnected-(U$8-NC4-Pad6)") (class "Default")
      (node (ref "U$8") (pin "6") (pinfunction "NC4_6") (pintype "bidirectional"))
    )
    (net (code "127") (name "unconnected-(U$8-NC5-Pad8)") (class "Default")
      (node (ref "U$8") (pin "8") (pinfunction "NC5_8") (pintype "bidirectional"))
    )
    (net (code "128") (name "unconnected-(U$8-NC6-Pad9)") (class "Default")
      (node (ref "U$8") (pin "9") (pinfunction "NC6_9") (pintype "bidirectional"))
    )
    (net (code "129") (name "unconnected-(U$8-NC7-Pad10)") (class "Default")
      (node (ref "U$8") (pin "10") (pinfunction "NC7_10") (pintype "bidirectional"))
    )
    (net (code "130") (name "unconnected-(U$8-NC8-Pad11)") (class "Default")
      (node (ref "U$8") (pin "11") (pinfunction "NC8_11") (pintype "bidirectional"))
    )
    (net (code "131") (name "unconnected-(U$8-NC9-Pad12)") (class "Default")
      (node (ref "U$8") (pin "12") (pinfunction "NC9_12") (pintype "bidirectional"))
    )
    (net (code "132") (name "unconnected-(U$8-NC10-Pad17)") (class "Default")
      (node (ref "U$8") (pin "17") (pinfunction "NC10_17") (pintype "bidirectional"))
    )
    (net (code "133") (name "unconnected-(U$8-NC11-Pad18)") (class "Default")
      (node (ref "U$8") (pin "18") (pinfunction "NC11_18") (pintype "bidirectional"))
    )
    (net (code "134") (name "unconnected-(U$8-NC12-Pad19)") (class "Default")
      (node (ref "U$8") (pin "19") (pinfunction "NC12_19") (pintype "bidirectional"))
    )
    (net (code "135") (name "unconnected-(U$8-OUT2-Pad20)") (class "Default")
      (node (ref "U$8") (pin "20") (pinfunction "OUT2_20") (pintype "bidirectional"))
    )
    (net (code "136") (name "unconnected-(U$8-PadTP)") (class "Default")
      (node (ref "U$8") (pin "TP") (pinfunction "TP_TP") (pintype "bidirectional"))
    )
  )
)
